# Line_5V.net
KiCad netlist of a schematic drawn in Altium Designer
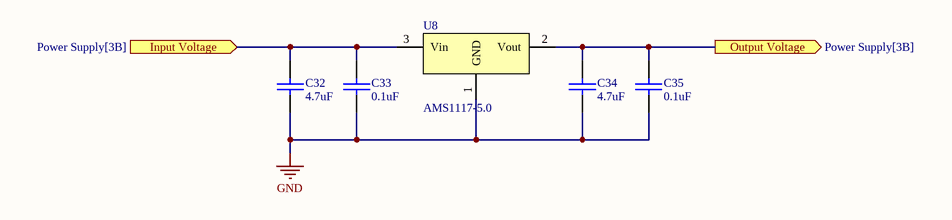
[diagram p0: Line 5V.SchDoc]

(export (version "E")
  (design (tool "Eeschema 10.0.6"))
  (components
    (comp (ref "C32")
      (value "4.7uF")
      (footprint "0805 Capicator")
      (description "4.7uF X5R 10% 25V 0805")
      (fields
        (field (name "MANUFACTURER") "Murata Manufacturing")
        (field (name "PART NUMBER") "GRM21BR61E475KA12L")
      )
      (libsource (lib "BRT_Components") (part "Cap 4.7uF (0805)"))
    )
    (comp (ref "C33")
      (value "0.1uF")
      (footprint "0805 Capicator")
      (description "0.1uF X7R 25V 10% 0805")
      (fields
        (field (name "MANUFACTURER") "Murata Manufacturing")
        (field (name "PART NUMBER") "GRM21BR71E104KA01L")
      )
      (libsource (lib "BRT_Components") (part "Cap 0.1uF (0805)"))
    )
    (comp (ref "C34")
      (value "4.7uF")
      (footprint "0805 Capicator")
      (description "4.7uF X5R 10% 25V 0805")
      (fields
        (field (name "MANUFACTURER") "Murata Manufacturing")
        (field (name "PART NUMBER") "GRM21BR61E475KA12L")
      )
      (libsource (lib "BRT_Components") (part "Cap 4.7uF (0805)"))
    )
    (comp (ref "C35")
      (value "0.1uF")
      (footprint "0805 Capicator")
      (description "0.1uF X7R 25V 10% 0805")
      (fields
        (field (name "MANUFACTURER") "Murata Manufacturing")
        (field (name "PART NUMBER") "GRM21BR71E104KA01L")
      )
      (libsource (lib "BRT_Components") (part "Cap 0.1uF (0805)"))
    )
    (comp (ref "U8")
      (value "AMS1117-5.0")
      (footprint "SOT-223")
      (description "1A 5V LOW DROPOUT VOLTAGE REGULATOR")
      (libsource (lib "Altium_Library") (part "LDO AMS1117-5.0"))
    )
  )
  (nets
    (net (code "1") (name "/Input Voltage") (class "Default")
      (node (ref "C32") (pin "2") (pinfunction "2_2") (pintype "passive"))
      (node (ref "C33") (pin "2") (pinfunction "2_2") (pintype "passive"))
      (node (ref "U8") (pin "3") (pinfunction "Vin_3") (pintype "power_in"))
    )
    (net (code "2") (name "/Output Voltage") (class "Default")
      (node (ref "C34") (pin "2") (pinfunction "2_2") (pintype "passive"))
      (node (ref "C35") (pin "2") (pinfunction "2_2") (pintype "passive"))
      (node (ref "U8") (pin "2") (pinfunction "Vout_2") (pintype "power_in"))
    )
    (net (code "3") (name "GND") (class "Default")
      (node (ref "C32") (pin "1") (pinfunction "1_1") (pintype "passive"))
      (node (ref "C33") (pin "1") (pinfunction "1_1") (pintype "passive"))
      (node (ref "C34") (pin "1") (pinfunction "1_1") (pintype "passive"))
      (node (ref "C35") (pin "1") (pinfunction "1_1") (pintype "passive"))
      (node (ref "U8") (pin "1") (pinfunction "GND_1") (pintype "power_in"))
    )
  )
)
